# saida_rele.net
KiCad netlist of a schematic drawn in Altium Designer
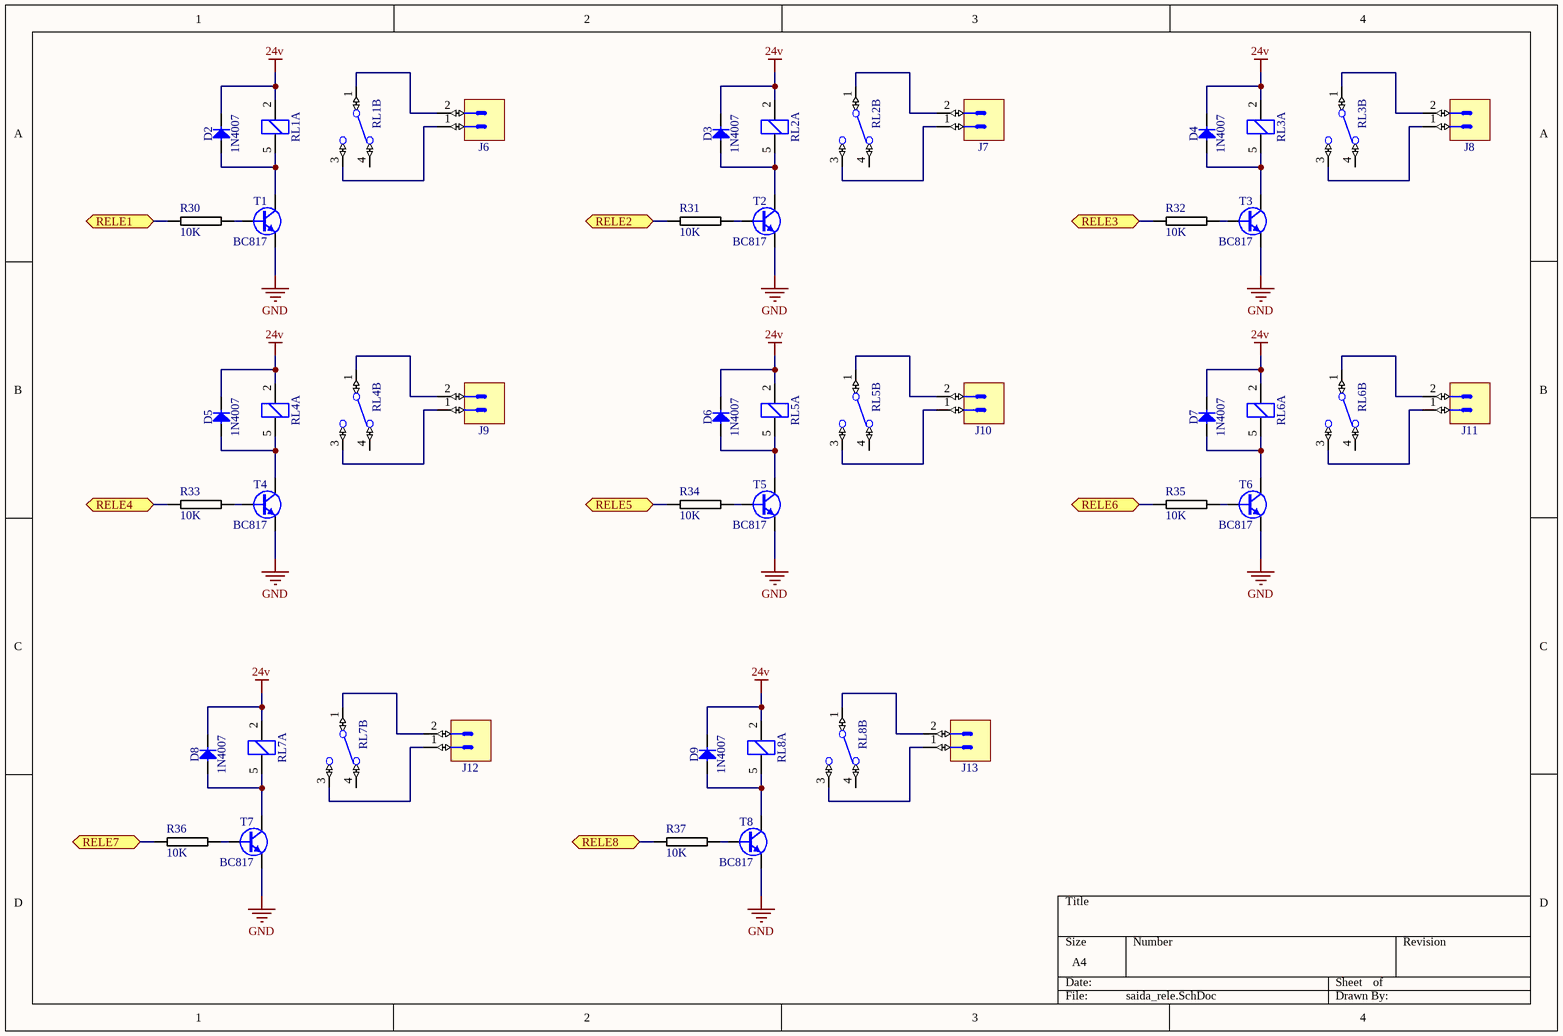
[diagram p0: saida_rele.SchDoc]

(export (version "E")
  (design (tool "Eeschema 10.0.6"))
  (components
    (comp (ref "D2")
      (value "1N4007")
      (footprint "DO-41")
      (description "Diode")
      (fields
        (field (name "VOLTAGE") "1000V")
        (field (name "POWER") "1A")
        (field (name "AUTHOR") "CERN DEM JLC")
      )
      (libsource (lib "ICs And Semiconductors") (part "Diode"))
    )
    (comp (ref "D3")
      (value "1N4007")
      (footprint "DO-41")
      (description "Diode")
      (fields
        (field (name "VOLTAGE") "1000V")
        (field (name "POWER") "1A")
        (field (name "AUTHOR") "CERN DEM JLC")
      )
      (libsource (lib "ICs And Semiconductors") (part "Diode"))
    )
    (comp (ref "D4")
      (value "1N4007")
      (footprint "DO-41")
      (description "Diode")
      (fields
        (field (name "VOLTAGE") "1000V")
        (field (name "POWER") "1A")
        (field (name "AUTHOR") "CERN DEM JLC")
      )
      (libsource (lib "ICs And Semiconductors") (part "Diode"))
    )
    (comp (ref "D5")
      (value "1N4007")
      (footprint "DO-41")
      (description "Diode")
      (fields
        (field (name "VOLTAGE") "1000V")
        (field (name "POWER") "1A")
        (field (name "AUTHOR") "CERN DEM JLC")
      )
      (libsource (lib "ICs And Semiconductors") (part "Diode"))
    )
    (comp (ref "D6")
      (value "1N4007")
      (footprint "DO-41")
      (description "Diode")
      (fields
        (field (name "VOLTAGE") "1000V")
        (field (name "POWER") "1A")
        (field (name "AUTHOR") "CERN DEM JLC")
      )
      (libsource (lib "ICs And Semiconductors") (part "Diode"))
    )
    (comp (ref "D7")
      (value "1N4007")
      (footprint "DO-41")
      (description "Diode")
      (fields
        (field (name "VOLTAGE") "1000V")
        (field (name "POWER") "1A")
        (field (name "AUTHOR") "CERN DEM JLC")
      )
      (libsource (lib "ICs And Semiconductors") (part "Diode"))
    )
    (comp (ref "D8")
      (value "1N4007")
      (footprint "DO-41")
      (description "Diode")
      (fields
        (field (name "VOLTAGE") "1000V")
        (field (name "POWER") "1A")
        (field (name "AUTHOR") "CERN DEM JLC")
      )
      (libsource (lib "ICs And Semiconductors") (part "Diode"))
    )
    (comp (ref "D9")
      (value "1N4007")
      (footprint "DO-41")
      (description "Diode")
      (fields
        (field (name "VOLTAGE") "1000V")
        (field (name "POWER") "1A")
        (field (name "AUTHOR") "CERN DEM JLC")
      )
      (libsource (lib "ICs And Semiconductors") (part "Diode"))
    )
    (comp (ref "J6")
      (value "~")
      (footprint "PHOENIX_1757242")
      (description "Connector 2 Male")
      (fields
        (field (name "PART NUMBER") "PHOENIX_1757242")
        (field (name "MANUFACTURER") "PHOENIX CONTACT")
        (field (name "AUTHOR") "CERN DEM JLC")
      )
      (libsource (lib "Connectors") (part "Connector 2 Male"))
    )
    (comp (ref "J7")
      (value "~")
      (footprint "PHOENIX_1757242")
      (description "Connector 2 Male")
      (fields
        (field (name "PART NUMBER") "PHOENIX_1757242")
        (field (name "MANUFACTURER") "PHOENIX CONTACT")
        (field (name "AUTHOR") "CERN DEM JLC")
      )
      (libsource (lib "Connectors") (part "Connector 2 Male"))
    )
    (comp (ref "J8")
      (value "~")
      (footprint "PHOENIX_1757242")
      (description "Connector 2 Male")
      (fields
        (field (name "PART NUMBER") "PHOENIX_1757242")
        (field (name "MANUFACTURER") "PHOENIX CONTACT")
        (field (name "AUTHOR") "CERN DEM JLC")
      )
      (libsource (lib "Connectors") (part "Connector 2 Male"))
    )
    (comp (ref "J9")
      (value "~")
      (footprint "PHOENIX_1757242")
      (description "Connector 2 Male")
      (fields
        (field (name "PART NUMBER") "PHOENIX_1757242")
        (field (name "MANUFACTURER") "PHOENIX CONTACT")
        (field (name "AUTHOR") "CERN DEM JLC")
      )
      (libsource (lib "Connectors") (part "Connector 2 Male"))
    )
    (comp (ref "J10")
      (value "~")
      (footprint "PHOENIX_1757242")
      (description "Connector 2 Male")
      (fields
        (field (name "PART NUMBER") "PHOENIX_1757242")
        (field (name "MANUFACTURER") "PHOENIX CONTACT")
        (field (name "AUTHOR") "CERN DEM JLC")
      )
      (libsource (lib "Connectors") (part "Connector 2 Male"))
    )
    (comp (ref "J11")
      (value "~")
      (footprint "PHOENIX_1757242")
      (description "Connector 2 Male")
      (fields
        (field (name "PART NUMBER") "PHOENIX_1757242")
        (field (name "MANUFACTURER") "PHOENIX CONTACT")
        (field (name "AUTHOR") "CERN DEM JLC")
      )
      (libsource (lib "Connectors") (part "Connector 2 Male"))
    )
    (comp (ref "J12")
      (value "~")
      (footprint "PHOENIX_1757242")
      (description "Connector 2 Male")
      (fields
        (field (name "PART NUMBER") "PHOENIX_1757242")
        (field (name "MANUFACTURER") "PHOENIX CONTACT")
        (field (name "AUTHOR") "CERN DEM JLC")
      )
      (libsource (lib "Connectors") (part "Connector 2 Male"))
    )
    (comp (ref "J13")
      (value "~")
      (footprint "PHOENIX_1757242")
      (description "Connector 2 Male")
      (fields
        (field (name "PART NUMBER") "PHOENIX_1757242")
        (field (name "MANUFACTURER") "PHOENIX CONTACT")
        (field (name "AUTHOR") "CERN DEM JLC")
      )
      (libsource (lib "Connectors") (part "Connector 2 Male"))
    )
    (comp (ref "R30")
      (value "10K")
      (footprint "0805R-10K")
      (description "RESISTOR 0805 1/4 WATT THIN FILM")
      (libsource (lib "vh_altium_library") (part "0805R-10K"))
    )
    (comp (ref "R31")
      (value "10K")
      (footprint "0805R-10K")
      (description "RESISTOR 0805 1/4 WATT THIN FILM")
      (libsource (lib "vh_altium_library") (part "0805R-10K"))
    )
    (comp (ref "R32")
      (value "10K")
      (footprint "0805R-10K")
      (description "RESISTOR 0805 1/4 WATT THIN FILM")
      (libsource (lib "vh_altium_library") (part "0805R-10K"))
    )
    (comp (ref "R33")
      (value "10K")
      (footprint "0805R-10K")
      (description "RESISTOR 0805 1/4 WATT THIN FILM")
      (libsource (lib "vh_altium_library") (part "0805R-10K"))
    )
    (comp (ref "R34")
      (value "10K")
      (footprint "0805R-10K")
      (description "RESISTOR 0805 1/4 WATT THIN FILM")
      (libsource (lib "vh_altium_library") (part "0805R-10K"))
    )
    (comp (ref "R35")
      (value "10K")
      (footprint "0805R-10K")
      (description "RESISTOR 0805 1/4 WATT THIN FILM")
      (libsource (lib "vh_altium_library") (part "0805R-10K"))
    )
    (comp (ref "R36")
      (value "10K")
      (footprint "0805R-10K")
      (description "RESISTOR 0805 1/4 WATT THIN FILM")
      (libsource (lib "vh_altium_library") (part "0805R-10K"))
    )
    (comp (ref "R37")
      (value "10K")
      (footprint "0805R-10K")
      (description "RESISTOR 0805 1/4 WATT THIN FILM")
      (libsource (lib "vh_altium_library") (part "0805R-10K"))
    )
    (comp (ref "RL1")
      (value "5VDC")
      (footprint "REL_PANASONIC_JS1")
      (description "10A SPDT PCB Relay, JS Serie")
      (fields
        (field (name "PART NUMBER") "REL_PANASONIC_JS1-5V-F")
        (field (name "MANUFACTURER") "PANASONIC")
        (field (name "AUTHOR") "CERN DEM JLC")
      )
      (libsource (lib "Eletro-mechanical") (part "REL_PANASONIC_JS1"))
    )
    (comp (ref "RL2")
      (value "5VDC")
      (footprint "REL_PANASONIC_JS1")
      (description "10A SPDT PCB Relay, JS Serie")
      (fields
        (field (name "PART NUMBER") "REL_PANASONIC_JS1-5V-F")
        (field (name "MANUFACTURER") "PANASONIC")
        (field (name "AUTHOR") "CERN DEM JLC")
      )
      (libsource (lib "") (part "REL_PANASONIC_JS1_1"))
    )
    (comp (ref "RL3")
      (value "5VDC")
      (footprint "REL_PANASONIC_JS1")
      (description "10A SPDT PCB Relay, JS Serie")
      (fields
        (field (name "PART NUMBER") "REL_PANASONIC_JS1-5V-F")
        (field (name "MANUFACTURER") "PANASONIC")
        (field (name "AUTHOR") "CERN DEM JLC")
      )
      (libsource (lib "") (part "REL_PANASONIC_JS1_1"))
    )
    (comp (ref "RL4")
      (value "5VDC")
      (footprint "REL_PANASONIC_JS1")
      (description "10A SPDT PCB Relay, JS Serie")
      (fields
        (field (name "PART NUMBER") "REL_PANASONIC_JS1-5V-F")
        (field (name "MANUFACTURER") "PANASONIC")
        (field (name "AUTHOR") "CERN DEM JLC")
      )
      (libsource (lib "") (part "REL_PANASONIC_JS1_1"))
    )
    (comp (ref "RL5")
      (value "5VDC")
      (footprint "REL_PANASONIC_JS1")
      (description "10A SPDT PCB Relay, JS Serie")
      (fields
        (field (name "PART NUMBER") "REL_PANASONIC_JS1-5V-F")
        (field (name "MANUFACTURER") "PANASONIC")
        (field (name "AUTHOR") "CERN DEM JLC")
      )
      (libsource (lib "") (part "REL_PANASONIC_JS1_1"))
    )
    (comp (ref "RL6")
      (value "5VDC")
      (footprint "REL_PANASONIC_JS1")
      (description "10A SPDT PCB Relay, JS Serie")
      (fields
        (field (name "PART NUMBER") "REL_PANASONIC_JS1-5V-F")
        (field (name "MANUFACTURER") "PANASONIC")
        (field (name "AUTHOR") "CERN DEM JLC")
      )
      (libsource (lib "") (part "REL_PANASONIC_JS1_1"))
    )
    (comp (ref "RL7")
      (value "5VDC")
      (footprint "REL_PANASONIC_JS1")
      (description "10A SPDT PCB Relay, JS Serie")
      (fields
        (field (name "PART NUMBER") "REL_PANASONIC_JS1-5V-F")
        (field (name "MANUFACTURER") "PANASONIC")
        (field (name "AUTHOR") "CERN DEM JLC")
      )
      (libsource (lib "Eletro-mechanical") (part "REL_PANASONIC_JS1"))
    )
    (comp (ref "RL8")
      (value "5VDC")
      (footprint "REL_PANASONIC_JS1")
      (description "10A SPDT PCB Relay, JS Serie")
      (fields
        (field (name "PART NUMBER") "REL_PANASONIC_JS1-5V-F")
        (field (name "MANUFACTURER") "PANASONIC")
        (field (name "AUTHOR") "CERN DEM JLC")
      )
      (libsource (lib "") (part "REL_PANASONIC_JS1_1"))
    )
    (comp (ref "T1")
      (value "BC817")
      (footprint "SOT95P230X110-3N")
      (description "NPN Transistor")
      (fields (field (name "MANUFACTURER") "NXP SEMICONDUCTORS") (field (name "AUTHOR") "CERN DEM JLC"))
      (libsource (lib "ICs And Semiconductors") (part "NPN B1 E2 C3"))
    )
    (comp (ref "T2")
      (value "BC817")
      (footprint "SOT95P230X110-3N")
      (description "NPN Transistor")
      (fields (field (name "MANUFACTURER") "NXP SEMICONDUCTORS") (field (name "AUTHOR") "CERN DEM JLC"))
      (libsource (lib "ICs And Semiconductors") (part "NPN B1 E2 C3"))
    )
    (comp (ref "T3")
      (value "BC817")
      (footprint "SOT95P230X110-3N")
      (description "NPN Transistor")
      (fields (field (name "MANUFACTURER") "NXP SEMICONDUCTORS") (field (name "AUTHOR") "CERN DEM JLC"))
      (libsource (lib "ICs And Semiconductors") (part "NPN B1 E2 C3"))
    )
    (comp (ref "T4")
      (value "BC817")
      (footprint "SOT95P230X110-3N")
      (description "NPN Transistor")
      (fields (field (name "MANUFACTURER") "NXP SEMICONDUCTORS") (field (name "AUTHOR") "CERN DEM JLC"))
      (libsource (lib "ICs And Semiconductors") (part "NPN B1 E2 C3"))
    )
    (comp (ref "T5")
      (value "BC817")
      (footprint "SOT95P230X110-3N")
      (description "NPN Transistor")
      (fields (field (name "MANUFACTURER") "NXP SEMICONDUCTORS") (field (name "AUTHOR") "CERN DEM JLC"))
      (libsource (lib "ICs And Semiconductors") (part "NPN B1 E2 C3"))
    )
    (comp (ref "T6")
      (value "BC817")
      (footprint "SOT95P230X110-3N")
      (description "NPN Transistor")
      (fields (field (name "MANUFACTURER") "NXP SEMICONDUCTORS") (field (name "AUTHOR") "CERN DEM JLC"))
      (libsource (lib "ICs And Semiconductors") (part "NPN B1 E2 C3"))
    )
    (comp (ref "T7")
      (value "BC817")
      (footprint "SOT95P230X110-3N")
      (description "NPN Transistor")
      (fields (field (name "MANUFACTURER") "NXP SEMICONDUCTORS") (field (name "AUTHOR") "CERN DEM JLC"))
      (libsource (lib "ICs And Semiconductors") (part "NPN B1 E2 C3"))
    )
    (comp (ref "T8")
      (value "BC817")
      (footprint "SOT95P230X110-3N")
      (description "NPN Transistor")
      (fields (field (name "MANUFACTURER") "NXP SEMICONDUCTORS") (field (name "AUTHOR") "CERN DEM JLC"))
      (libsource (lib "ICs And Semiconductors") (part "NPN B1 E2 C3"))
    )
  )
  (nets
    (net (code "1") (name "/RELE1") (class "Default") (node (ref "R30") (pin "1") (pintype "passive")))
    (net (code "2") (name "/RELE2") (class "Default") (node (ref "R31") (pin "1") (pintype "passive")))
    (net (code "3") (name "/RELE3") (class "Default") (node (ref "R32") (pin "1") (pintype "passive")))
    (net (code "4") (name "/RELE4") (class "Default") (node (ref "R33") (pin "1") (pintype "passive")))
    (net (code "5") (name "/RELE5") (class "Default") (node (ref "R34") (pin "1") (pintype "passive")))
    (net (code "6") (name "/RELE6") (class "Default") (node (ref "R35") (pin "1") (pintype "passive")))
    (net (code "7") (name "/RELE7") (class "Default") (node (ref "R36") (pin "1") (pintype "passive")))
    (net (code "8") (name "/RELE8") (class "Default") (node (ref "R37") (pin "1") (pintype "passive")))
    (net (code "9") (name "24v") (class "Default")
      (node (ref "D2") (pin "1") (pinfunction "C_1") (pintype "passive"))
      (node (ref "D3") (pin "1") (pinfunction "C_1") (pintype "passive"))
      (node (ref "D4") (pin "1") (pinfunction "C_1") (pintype "passive"))
      (node (ref "D5") (pin "1") (pinfunction "C_1") (pintype "passive"))
      (node (ref "D6") (pin "1") (pinfunction "C_1") (pintype "passive"))
      (node (ref "D7") (pin "1") (pinfunction "C_1") (pintype "passive"))
      (node (ref "D8") (pin "1") (pinfunction "C_1") (pintype "passive"))
      (node (ref "D9") (pin "1") (pinfunction "C_1") (pintype "passive"))
      (node (ref "RL1") (pin "2") (pinfunction "COIL_2") (pintype "passive"))
      (node (ref "RL2") (pin "2") (pinfunction "COIL_2") (pintype "passive"))
      (node (ref "RL3") (pin "2") (pinfunction "COIL_2") (pintype "passive"))
      (node (ref "RL4") (pin "2") (pinfunction "COIL_2") (pintype "passive"))
      (node (ref "RL5") (pin "2") (pinfunction "COIL_2") (pintype "passive"))
      (node (ref "RL6") (pin "2") (pinfunction "COIL_2") (pintype "passive"))
      (node (ref "RL7") (pin "2") (pinfunction "COIL_2") (pintype "passive"))
      (node (ref "RL8") (pin "2") (pinfunction "COIL_2") (pintype "passive"))
    )
    (net (code "10") (name "GND") (class "Default")
      (node (ref "T1") (pin "2") (pinfunction "E_2") (pintype "passive"))
      (node (ref "T2") (pin "2") (pinfunction "E_2") (pintype "passive"))
      (node (ref "T3") (pin "2") (pinfunction "E_2") (pintype "passive"))
      (node (ref "T4") (pin "2") (pinfunction "E_2") (pintype "passive"))
      (node (ref "T5") (pin "2") (pinfunction "E_2") (pintype "passive"))
      (node (ref "T6") (pin "2") (pinfunction "E_2") (pintype "passive"))
      (node (ref "T7") (pin "2") (pinfunction "E_2") (pintype "passive"))
      (node (ref "T8") (pin "2") (pinfunction "E_2") (pintype "passive"))
    )
    (net (code "11") (name "Net-(D2-A)") (class "Default")
      (node (ref "D2") (pin "2") (pinfunction "A_2") (pintype "passive"))
      (node (ref "RL1") (pin "5") (pinfunction "COIL_5") (pintype "passive"))
      (node (ref "T1") (pin "3") (pinfunction "C_3") (pintype "passive"))
    )
    (net (code "12") (name "Net-(D3-A)") (class "Default")
      (node (ref "D3") (pin "2") (pinfunction "A_2") (pintype "passive"))
      (node (ref "RL2") (pin "5") (pinfunction "COIL_5") (pintype "passive"))
      (node (ref "T2") (pin "3") (pinfunction "C_3") (pintype "passive"))
    )
    (net (code "13") (name "Net-(D4-A)") (class "Default")
      (node (ref "D4") (pin "2") (pinfunction "A_2") (pintype "passive"))
      (node (ref "RL3") (pin "5") (pinfunction "COIL_5") (pintype "passive"))
      (node (ref "T3") (pin "3") (pinfunction "C_3") (pintype "passive"))
    )
    (net (code "14") (name "Net-(D5-A)") (class "Default")
      (node (ref "D5") (pin "2") (pinfunction "A_2") (pintype "passive"))
      (node (ref "RL4") (pin "5") (pinfunction "COIL_5") (pintype "passive"))
      (node (ref "T4") (pin "3") (pinfunction "C_3") (pintype "passive"))
    )
    (net (code "15") (name "Net-(D6-A)") (class "Default")
      (node (ref "D6") (pin "2") (pinfunction "A_2") (pintype "passive"))
      (node (ref "RL5") (pin "5") (pinfunction "COIL_5") (pintype "passive"))
      (node (ref "T5") (pin "3") (pinfunction "C_3") (pintype "passive"))
    )
    (net (code "16") (name "Net-(D7-A)") (class "Default")
      (node (ref "D7") (pin "2") (pinfunction "A_2") (pintype "passive"))
      (node (ref "RL6") (pin "5") (pinfunction "COIL_5") (pintype "passive"))
      (node (ref "T6") (pin "3") (pinfunction "C_3") (pintype "passive"))
    )
    (net (code "17") (name "Net-(D8-A)") (class "Default")
      (node (ref "D8") (pin "2") (pinfunction "A_2") (pintype "passive"))
      (node (ref "RL7") (pin "5") (pinfunction "COIL_5") (pintype "passive"))
      (node (ref "T7") (pin "3") (pinfunction "C_3") (pintype "passive"))
    )
    (net (code "18") (name "Net-(D9-A)") (class "Default")
      (node (ref "D9") (pin "2") (pinfunction "A_2") (pintype "passive"))
      (node (ref "RL8") (pin "5") (pinfunction "COIL_5") (pintype "passive"))
      (node (ref "T8") (pin "3") (pinfunction "C_3") (pintype "passive"))
    )
    (net (code "19") (name "Net-(RL1B-C)") (class "Default")
      (node (ref "J6") (pin "2") (pinfunction "2_2") (pintype "bidirectional"))
      (node (ref "RL1") (pin "1") (pinfunction "C_1") (pintype "bidirectional"))
    )
    (net (code "20") (name "Net-(RL1B-NO)") (class "Default")
      (node (ref "J6") (pin "1") (pinfunction "1_1") (pintype "bidirectional"))
      (node (ref "RL1") (pin "3") (pinfunction "NO_3") (pintype "bidirectional"))
    )
    (net (code "21") (name "Net-(RL2B-C)") (class "Default")
      (node (ref "J7") (pin "2") (pinfunction "2_2") (pintype "bidirectional"))
      (node (ref "RL2") (pin "1") (pinfunction "C_1") (pintype "bidirectional"))
    )
    (net (code "22") (name "Net-(RL2B-NO)") (class "Default")
      (node (ref "J7") (pin "1") (pinfunction "1_1") (pintype "bidirectional"))
      (node (ref "RL2") (pin "3") (pinfunction "NO_3") (pintype "bidirectional"))
    )
    (net (code "23") (name "Net-(RL3B-C)") (class "Default")
      (node (ref "J8") (pin "2") (pinfunction "2_2") (pintype "bidirectional"))
      (node (ref "RL3") (pin "1") (pinfunction "C_1") (pintype "bidirectional"))
    )
    (net (code "24") (name "Net-(RL3B-NO)") (class "Default")
      (node (ref "J8") (pin "1") (pinfunction "1_1") (pintype "bidirectional"))
      (node (ref "RL3") (pin "3") (pinfunction "NO_3") (pintype "bidirectional"))
    )
    (net (code "25") (name "Net-(RL4B-C)") (class "Default")
      (node (ref "J9") (pin "2") (pinfunction "2_2") (pintype "bidirectional"))
      (node (ref "RL4") (pin "1") (pinfunction "C_1") (pintype "bidirectional"))
    )
    (net (code "26") (name "Net-(RL4B-NO)") (class "Default")
      (node (ref "J9") (pin "1") (pinfunction "1_1") (pintype "bidirectional"))
      (node (ref "RL4") (pin "3") (pinfunction "NO_3") (pintype "bidirectional"))
    )
    (net (code "27") (name "Net-(RL5B-C)") (class "Default")
      (node (ref "J10") (pin "2") (pinfunction "2_2") (pintype "bidirectional"))
      (node (ref "RL5") (pin "1") (pinfunction "C_1") (pintype "bidirectional"))
    )
    (net (code "28") (name "Net-(RL5B-NO)") (class "Default")
      (node (ref "J10") (pin "1") (pinfunction "1_1") (pintype "bidirectional"))
      (node (ref "RL5") (pin "3") (pinfunction "NO_3") (pintype "bidirectional"))
    )
    (net (code "29") (name "Net-(RL6B-C)") (class "Default")
      (node (ref "J11") (pin "2") (pinfunction "2_2") (pintype "bidirectional"))
      (node (ref "RL6") (pin "1") (pinfunction "C_1") (pintype "bidirectional"))
    )
    (net (code "30") (name "Net-(RL6B-NO)") (class "Default")
      (node (ref "J11") (pin "1") (pinfunction "1_1") (pintype "bidirectional"))
      (node (ref "RL6") (pin "3") (pinfunction "NO_3") (pintype "bidirectional"))
    )
    (net (code "31") (name "Net-(RL7B-C)") (class "Default")
      (node (ref "J12") (pin "2") (pinfunction "2_2") (pintype "bidirectional"))
      (node (ref "RL7") (pin "1") (pinfunction "C_1") (pintype "bidirectional"))
    )
    (net (code "32") (name "Net-(RL7B-NO)") (class "Default")
      (node (ref "J12") (pin "1") (pinfunction "1_1") (pintype "bidirectional"))
      (node (ref "RL7") (pin "3") (pinfunction "NO_3") (pintype "bidirectional"))
    )
    (net (code "33") (name "Net-(RL8B-C)") (class "Default")
      (node (ref "J13") (pin "2") (pinfunction "2_2") (pintype "bidirectional"))
      (node (ref "RL8") (pin "1") (pinfunction "C_1") (pintype "bidirectional"))
    )
    (net (code "34") (name "Net-(RL8B-NO)") (class "Default")
      (node (ref "J13") (pin "1") (pinfunction "1_1") (pintype "bidirectional"))
      (node (ref "RL8") (pin "3") (pinfunction "NO_3") (pintype "bidirectional"))
    )
    (net (code "35") (name "Net-(T1-B)") (class "Default")
      (node (ref "R30") (pin "2") (pintype "passive"))
      (node (ref "T1") (pin "1") (pinfunction "B_1") (pintype "passive"))
    )
    (net (code "36") (name "Net-(T2-B)") (class "Default")
      (node (ref "R31") (pin "2") (pintype "passive"))
      (node (ref "T2") (pin "1") (pinfunction "B_1") (pintype "passive"))
    )
    (net (code "37") (name "Net-(T3-B)") (class "Default")
      (node (ref "R32") (pin "2") (pintype "passive"))
      (node (ref "T3") (pin "1") (pinfunction "B_1") (pintype "passive"))
    )
    (net (code "38") (name "Net-(T4-B)") (class "Default")
      (node (ref "R33") (pin "2") (pintype "passive"))
      (node (ref "T4") (pin "1") (pinfunction "B_1") (pintype "passive"))
    )
    (net (code "39") (name "Net-(T5-B)") (class "Default")
      (node (ref "R34") (pin "2") (pintype "passive"))
      (node (ref "T5") (pin "1") (pinfunction "B_1") (pintype "passive"))
    )
    (net (code "40") (name "Net-(T6-B)") (class "Default")
      (node (ref "R35") (pin "2") (pintype "passive"))
      (node (ref "T6") (pin "1") (pinfunction "B_1") (pintype "passive"))
    )
    (net (code "41") (name "Net-(T7-B)") (class "Default")
      (node (ref "R36") (pin "2") (pintype "passive"))
      (node (ref "T7") (pin "1") (pinfunction "B_1") (pintype "passive"))
    )
    (net (code "42") (name "Net-(T8-B)") (class "Default")
      (node (ref "R37") (pin "2") (pintype "passive"))
      (node (ref "T8") (pin "1") (pinfunction "B_1") (pintype "passive"))
    )
    (net (code "43") (name "unconnected-(RL1B-NC-Pad4)") (class "Default")
      (node (ref "RL1") (pin "4") (pinfunction "NC_4") (pintype "bidirectional"))
    )
    (net (code "44") (name "unconnected-(RL2B-NC-Pad4)") (class "Default")
      (node (ref "RL2") (pin "4") (pinfunction "NC_4") (pintype "bidirectional"))
    )
    (net (code "45") (name "unconnected-(RL3B-NC-Pad4)") (class "Default")
      (node (ref "RL3") (pin "4") (pinfunction "NC_4") (pintype "bidirectional"))
    )
    (net (code "46") (name "unconnected-(RL4B-NC-Pad4)") (class "Default")
      (node (ref "RL4") (pin "4") (pinfunction "NC_4") (pintype "bidirectional"))
    )
    (net (code "47") (name "unconnected-(RL5B-NC-Pad4)") (class "Default")
      (node (ref "RL5") (pin "4") (pinfunction "NC_4") (pintype "bidirectional"))
    )
    (net (code "48") (name "unconnected-(RL6B-NC-Pad4)") (class "Default")
      (node (ref "RL6") (pin "4") (pinfunction "NC_4") (pintype "bidirectional"))
    )
    (net (code "49") (name "unconnected-(RL7B-NC-Pad4)") (class "Default")
      (node (ref "RL7") (pin "4") (pinfunction "NC_4") (pintype "bidirectional"))
    )
    (net (code "50") (name "unconnected-(RL8B-NC-Pad4)") (class "Default")
      (node (ref "RL8") (pin "4") (pinfunction "NC_4") (pintype "bidirectional"))
    )
  )
)
